# Hackcard_Nov_12_2025.net
KiCad netlist of a schematic drawn in EasyEDA
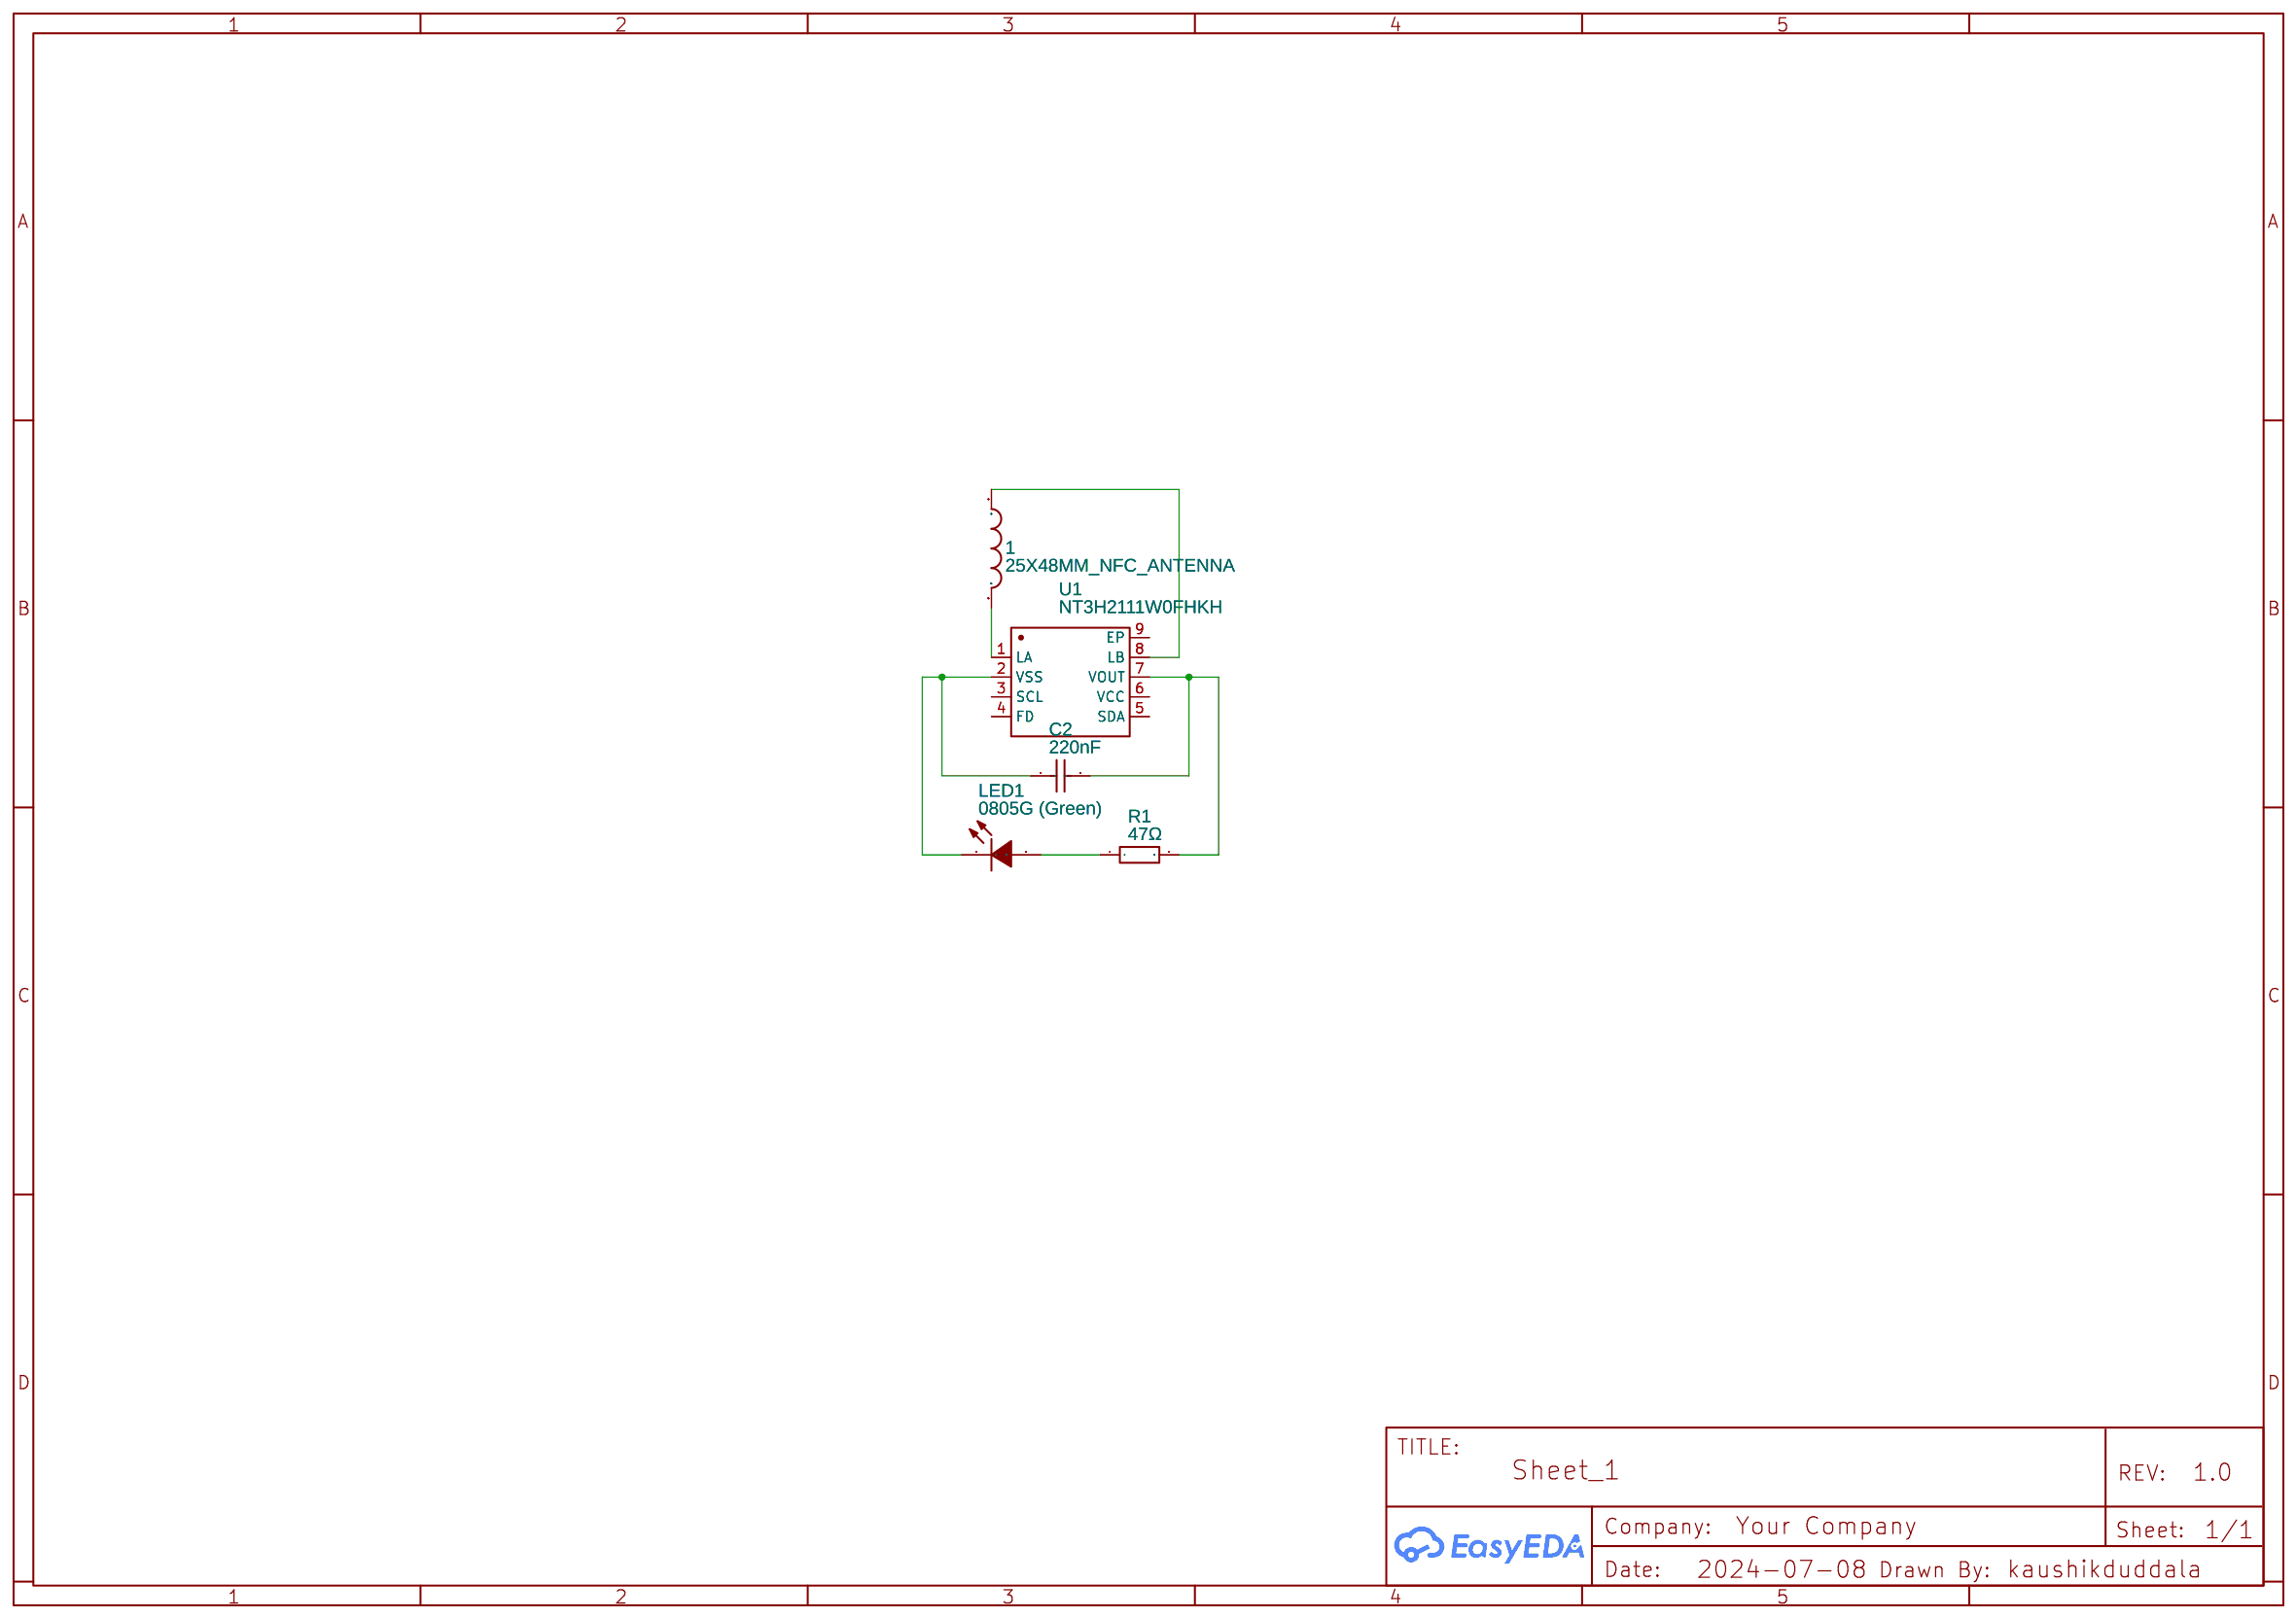
[diagram p0: schematic sheet]

(export (version "E")
  (design (tool "Eeschema 10.0.6"))
  (components
    (comp (ref "1") (value "25X48MM_NFC_ANTENNA") (libsource (lib "") (part "25X48MM_NFC_ANTENNA")))
    (comp (ref "C2")
      (value "220nF")
      (fields
        (field (name "Manufacturer Part") "CL10B224KA8NNNC")
        (field (name "Manufacturer") "SAMSUNG(三星)")
      )
      (libsource (lib "") (part "CL10B224KA8NNNC"))
    )
    (comp (ref "LED1")
      (value "0805G (Green)")
      (fields (field (name "Manufacturer Part") "KT-0805G") (field (name "Manufacturer") "KENTO"))
      (libsource (lib "") (part "0805G (Green)"))
    )
    (comp (ref "R1")
      (value "47Ω")
      (fields
        (field (name "Manufacturer Part") "0603WAF470JT5E")
        (field (name "Manufacturer") "UNI-ROYAL(厚声)")
      )
      (libsource (lib "") (part "0603WAF470JT5E"))
    )
    (comp (ref "U1")
      (value "NT3H2111W0FHKH")
      (fields (field (name "Manufacturer") "NXP(恩智浦)"))
      (libsource (lib "") (part "NT3H2111W0FHKH"))
    )
  )
  (nets
    (net (code "1") (name "Net-(LED1-A)") (class "Default")
      (node (ref "LED1") (pin "1") (pinfunction "A_1") (pintype "unspecified"))
      (node (ref "R1") (pin "1") (pinfunction "1_1") (pintype "input"))
    )
    (net (code "2") (name "Net-(LED1-K)") (class "Default")
      (node (ref "C2") (pin "1") (pinfunction "1_1") (pintype "input"))
      (node (ref "LED1") (pin "2") (pinfunction "K_2") (pintype "unspecified"))
      (node (ref "U1") (pin "2") (pinfunction "VSS_2") (pintype "unspecified"))
    )
    (net (code "3") (name "Net-(U1-LA)") (class "Default")
      (node (ref "1") (pin "P$2") (pinfunction "P$2_P$2") (pintype "bidirectional"))
      (node (ref "U1") (pin "1") (pinfunction "LA_1") (pintype "unspecified"))
    )
    (net (code "4") (name "Net-(U1-LB)") (class "Default")
      (node (ref "1") (pin "P$1") (pinfunction "P$1_P$1") (pintype "bidirectional"))
      (node (ref "U1") (pin "8") (pinfunction "LB_8") (pintype "unspecified"))
    )
    (net (code "5") (name "Net-(U1-VOUT)") (class "Default")
      (node (ref "C2") (pin "2") (pinfunction "2_2") (pintype "input"))
      (node (ref "R1") (pin "2") (pinfunction "2_2") (pintype "input"))
      (node (ref "U1") (pin "7") (pinfunction "VOUT_7") (pintype "unspecified"))
    )
    (net (code "6") (name "unconnected-(U1-EP-Pad9)") (class "Default")
      (node (ref "U1") (pin "9") (pinfunction "EP_9") (pintype "unspecified"))
    )
    (net (code "7") (name "unconnected-(U1-FD-Pad4)") (class "Default")
      (node (ref "U1") (pin "4") (pinfunction "FD_4") (pintype "unspecified"))
    )
    (net (code "8") (name "unconnected-(U1-SCL-Pad3)") (class "Default")
      (node (ref "U1") (pin "3") (pinfunction "SCL_3") (pintype "unspecified"))
    )
    (net (code "9") (name "unconnected-(U1-SDA-Pad5)") (class "Default")
      (node (ref "U1") (pin "5") (pinfunction "SDA_5") (pintype "unspecified"))
    )
    (net (code "10") (name "unconnected-(U1-VCC-Pad6)") (class "Default")
      (node (ref "U1") (pin "6") (pinfunction "VCC_6") (pintype "unspecified"))
    )
  )
)
